# Driver_v0.net
KiCad netlist of a schematic drawn in Altium Designer
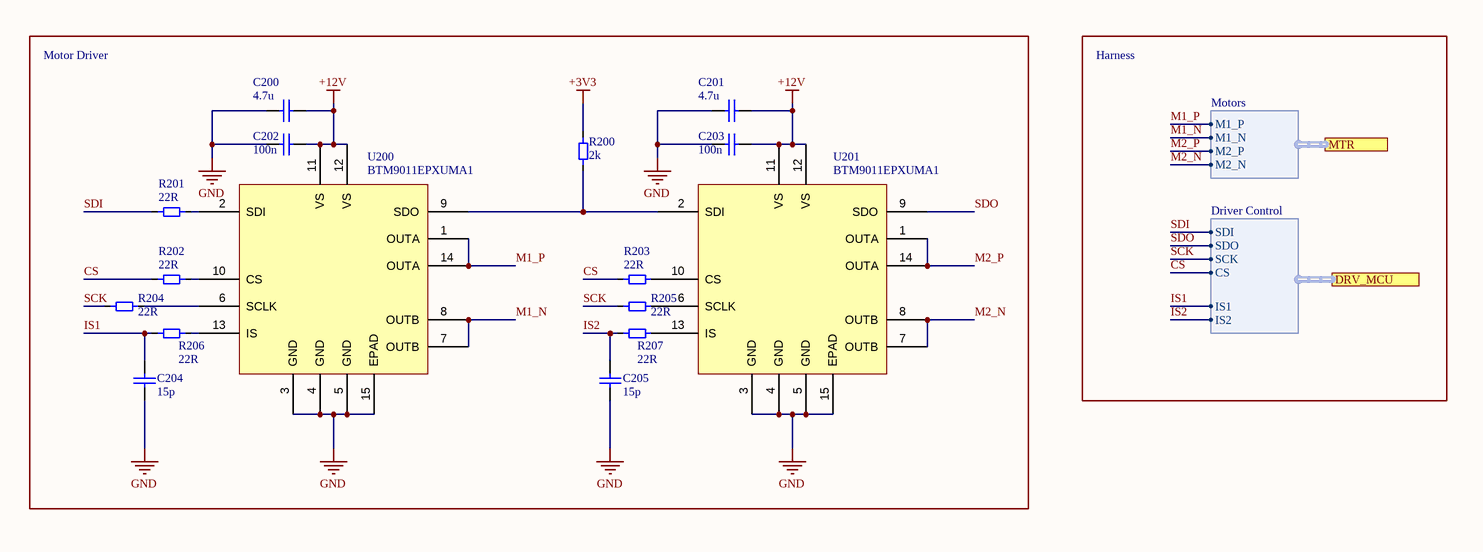
[diagram p0: Driver_v0.SchDoc, right]

(export (version "E")
  (design (tool "Eeschema 10.0.6"))
  (components
    (comp (ref "C200")
      (value "4.7u")
      (footprint "MLCC_0603_M")
      (description "MLCC, 0603, 4.7u, 10%, 35V, X5R")
      (fields (field (name "TOLERANCE") "10%") (field (name "VOLTAGE") "35V"))
      (libsource (lib "Krakul Vault") (part "CAPACITOR_NONPOL_IEC"))
    )
    (comp (ref "C201")
      (value "4.7u")
      (footprint "MLCC_0603_M")
      (description "MLCC, 0603, 4.7u, 10%, 35V, X5R")
      (fields (field (name "TOLERANCE") "10%") (field (name "VOLTAGE") "35V"))
      (libsource (lib "Krakul Vault") (part "CAPACITOR_NONPOL_IEC"))
    )
    (comp (ref "C202")
      (value "100n")
      (footprint "MLCC_0603_M")
      (description "MLCC, 0603, 100n, 10%, 35V, X7R")
      (fields (field (name "MANUFACTURER") "Any") (field (name "VOLTAGE") "35V"))
      (libsource (lib "Krakul Vault") (part "CAPACITOR_NONPOL_IEC"))
    )
    (comp (ref "C203")
      (value "100n")
      (footprint "MLCC_0603_M")
      (description "MLCC, 0603, 100n, 10%, 35V, X7R")
      (fields (field (name "MANUFACTURER") "Any") (field (name "VOLTAGE") "35V"))
      (libsource (lib "Krakul Vault") (part "CAPACITOR_NONPOL_IEC"))
    )
    (comp (ref "C204")
      (value "15p")
      (footprint "MLCC_0603_M")
      (description "MLCC, 0603, 15p, 5%, 50V, C0G/NP0")
      (fields (field (name "MANUFACTURER") "Any") (field (name "VOLTAGE") "50V"))
      (libsource (lib "Krakul Vault") (part "CAPACITOR_NONPOL_IEC"))
    )
    (comp (ref "C205")
      (value "15p")
      (footprint "MLCC_0603_M")
      (description "MLCC, 0603, 15p, 5%, 50V, C0G/NP0")
      (fields (field (name "MANUFACTURER") "Any") (field (name "VOLTAGE") "50V"))
      (libsource (lib "Krakul Vault") (part "CAPACITOR_NONPOL_IEC"))
    )
    (comp (ref "R200")
      (value "2k")
      (footprint "Resistor_0603_M")
      (description "Resistor, 0603, 2k, 1%, 1/10W")
      (fields (field (name "MANUFACTURER") "Any") (field (name "POWER") "100mW"))
      (libsource (lib "Krakul Vault") (part "RESISTOR_GENERIC_IEC"))
    )
    (comp (ref "R201")
      (value "22R")
      (footprint "Resistor_0603_M")
      (description "Resistor, 0603, 22R, 1%, 1/10W")
      (fields (field (name "TOLERANCE") "1%") (field (name "MANUFACTURER") "Any"))
      (libsource (lib "Krakul Vault") (part "RESISTOR_GENERIC_IEC"))
    )
    (comp (ref "R202")
      (value "22R")
      (footprint "Resistor_0603_M")
      (description "Resistor, 0603, 22R, 1%, 1/10W")
      (fields (field (name "TOLERANCE") "1%") (field (name "MANUFACTURER") "Any"))
      (libsource (lib "Krakul Vault") (part "RESISTOR_GENERIC_IEC"))
    )
    (comp (ref "R203")
      (value "22R")
      (footprint "Resistor_0603_M")
      (description "Resistor, 0603, 22R, 1%, 1/10W")
      (fields (field (name "TOLERANCE") "1%") (field (name "MANUFACTURER") "Any"))
      (libsource (lib "Krakul Vault") (part "RESISTOR_GENERIC_IEC"))
    )
    (comp (ref "R204")
      (value "22R")
      (footprint "Resistor_0603_M")
      (description "Resistor, 0603, 22R, 1%, 1/10W")
      (fields (field (name "TOLERANCE") "1%") (field (name "MANUFACTURER") "Any"))
      (libsource (lib "Krakul Vault") (part "RESISTOR_GENERIC_IEC"))
    )
    (comp (ref "R205")
      (value "22R")
      (footprint "Resistor_0603_M")
      (description "Resistor, 0603, 22R, 1%, 1/10W")
      (fields (field (name "TOLERANCE") "1%") (field (name "MANUFACTURER") "Any"))
      (libsource (lib "Krakul Vault") (part "RESISTOR_GENERIC_IEC"))
    )
    (comp (ref "R206")
      (value "22R")
      (footprint "Resistor_0603_M")
      (description "Resistor, 0603, 22R, 1%, 1/10W")
      (fields (field (name "TOLERANCE") "1%") (field (name "MANUFACTURER") "Any"))
      (libsource (lib "Krakul Vault") (part "RESISTOR_GENERIC_IEC"))
    )
    (comp (ref "R207")
      (value "22R")
      (footprint "Resistor_0603_M")
      (description "Resistor, 0603, 22R, 1%, 1/10W")
      (fields (field (name "TOLERANCE") "1%") (field (name "MANUFACTURER") "Any"))
      (libsource (lib "Krakul Vault") (part "RESISTOR_GENERIC_IEC"))
    )
    (comp (ref "U200")
      (value "BTM9011EPXUMA1")
      (footprint "BTM9011EPXUMA1")
      (description "DC Mtr Drive, Brush, 150DEGC, TSSOPEP-14 Rohs Compliant: Yes")
      (fields (field (name "MANUFACTURER") "Infineon Technologies"))
      (libsource (lib "Krakul Vault") (part "BTM9011EPXUMA1"))
    )
    (comp (ref "U201")
      (value "BTM9011EPXUMA1")
      (footprint "BTM9011EPXUMA1")
      (description "DC Mtr Drive, Brush, 150DEGC, TSSOPEP-14 Rohs Compliant: Yes")
      (fields (field (name "MANUFACTURER") "Infineon Technologies"))
      (libsource (lib "Krakul Vault") (part "BTM9011EPXUMA1"))
    )
  )
  (nets
    (net (code "4") (name "+3V3") (class "Default")
      (node (ref "R200") (pin "2") (pinfunction "2_2") (pintype "passive"))
    )
    (net (code "5") (name "+12V") (class "Default")
      (node (ref "C200") (pin "2") (pinfunction "2_2") (pintype "passive"))
      (node (ref "C201") (pin "2") (pinfunction "2_2") (pintype "passive"))
      (node (ref "C202") (pin "2") (pinfunction "2_2") (pintype "passive"))
      (node (ref "C203") (pin "2") (pinfunction "2_2") (pintype "passive"))
      (node (ref "U200") (pin "11") (pinfunction "VS_11") (pintype "passive"))
      (node (ref "U200") (pin "12") (pinfunction "VS_12") (pintype "passive"))
      (node (ref "U201") (pin "11") (pinfunction "VS_11") (pintype "passive"))
      (node (ref "U201") (pin "12") (pinfunction "VS_12") (pintype "passive"))
    )
    (net (code "6") (name "/CS") (class "Default")
      (node (ref "R202") (pin "1") (pinfunction "1_1") (pintype "passive"))
      (node (ref "R203") (pin "1") (pinfunction "1_1") (pintype "passive"))
    )
    (net (code "7") (name "/IS1") (class "Default")
      (node (ref "C204") (pin "1") (pinfunction "1_1") (pintype "passive"))
      (node (ref "R206") (pin "1") (pinfunction "1_1") (pintype "passive"))
    )
    (net (code "8") (name "/IS2") (class "Default")
      (node (ref "C205") (pin "1") (pinfunction "1_1") (pintype "passive"))
      (node (ref "R207") (pin "1") (pinfunction "1_1") (pintype "passive"))
    )
    (net (code "9") (name "/M1_N") (class "Default")
      (node (ref "U200") (pin "7") (pinfunction "OUTB_7") (pintype "passive"))
      (node (ref "U200") (pin "8") (pinfunction "OUTB_8") (pintype "passive"))
    )
    (net (code "10") (name "/M1_P") (class "Default")
      (node (ref "U200") (pin "1") (pinfunction "OUTA_1") (pintype "passive"))
      (node (ref "U200") (pin "14") (pinfunction "OUTA_14") (pintype "passive"))
    )
    (net (code "11") (name "/M2_N") (class "Default")
      (node (ref "U201") (pin "7") (pinfunction "OUTB_7") (pintype "passive"))
      (node (ref "U201") (pin "8") (pinfunction "OUTB_8") (pintype "passive"))
    )
    (net (code "12") (name "/M2_P") (class "Default")
      (node (ref "U201") (pin "1") (pinfunction "OUTA_1") (pintype "passive"))
      (node (ref "U201") (pin "14") (pinfunction "OUTA_14") (pintype "passive"))
    )
    (net (code "13") (name "/SCK") (class "Default")
      (node (ref "R204") (pin "1") (pinfunction "1_1") (pintype "passive"))
      (node (ref "R205") (pin "1") (pinfunction "1_1") (pintype "passive"))
    )
    (net (code "14") (name "/SDI") (class "Default")
      (node (ref "R201") (pin "1") (pinfunction "1_1") (pintype "passive"))
    )
    (net (code "15") (name "/SDO") (class "Default")
      (node (ref "U201") (pin "9") (pinfunction "SDO_9") (pintype "passive"))
    )
    (net (code "18") (name "GND") (class "Default")
      (node (ref "C200") (pin "1") (pinfunction "1_1") (pintype "passive"))
      (node (ref "C201") (pin "1") (pinfunction "1_1") (pintype "passive"))
      (node (ref "C202") (pin "1") (pinfunction "1_1") (pintype "passive"))
      (node (ref "C203") (pin "1") (pinfunction "1_1") (pintype "passive"))
      (node (ref "C204") (pin "2") (pinfunction "2_2") (pintype "passive"))
      (node (ref "C205") (pin "2") (pinfunction "2_2") (pintype "passive"))
      (node (ref "U200") (pin "15") (pinfunction "EPAD_15") (pintype "passive"))
      (node (ref "U200") (pin "3") (pinfunction "GND_3") (pintype "passive"))
      (node (ref "U200") (pin "4") (pinfunction "GND_4") (pintype "passive"))
      (node (ref "U200") (pin "5") (pinfunction "GND_5") (pintype "passive"))
      (node (ref "U201") (pin "15") (pinfunction "EPAD_15") (pintype "passive"))
      (node (ref "U201") (pin "3") (pinfunction "GND_3") (pintype "passive"))
      (node (ref "U201") (pin "4") (pinfunction "GND_4") (pintype "passive"))
      (node (ref "U201") (pin "5") (pinfunction "GND_5") (pintype "passive"))
    )
    (net (code "19") (name "Net-(U200-CS)") (class "Default")
      (node (ref "R202") (pin "2") (pinfunction "2_2") (pintype "passive"))
      (node (ref "U200") (pin "10") (pinfunction "CS_10") (pintype "passive"))
    )
    (net (code "20") (name "Net-(U200-IS)") (class "Default")
      (node (ref "R206") (pin "2") (pinfunction "2_2") (pintype "passive"))
      (node (ref "U200") (pin "13") (pinfunction "IS_13") (pintype "passive"))
    )
    (net (code "21") (name "Net-(U200-SCLK)") (class "Default")
      (node (ref "R204") (pin "2") (pinfunction "2_2") (pintype "passive"))
      (node (ref "U200") (pin "6") (pinfunction "SCLK_6") (pintype "passive"))
    )
    (net (code "22") (name "Net-(U200-SDI)") (class "Default")
      (node (ref "R201") (pin "2") (pinfunction "2_2") (pintype "passive"))
      (node (ref "U200") (pin "2") (pinfunction "SDI_2") (pintype "passive"))
    )
    (net (code "23") (name "Net-(U200-SDO)") (class "Default")
      (node (ref "R200") (pin "1") (pinfunction "1_1") (pintype "passive"))
      (node (ref "U200") (pin "9") (pinfunction "SDO_9") (pintype "passive"))
      (node (ref "U201") (pin "2") (pinfunction "SDI_2") (pintype "passive"))
    )
    (net (code "24") (name "Net-(U201-CS)") (class "Default")
      (node (ref "R203") (pin "2") (pinfunction "2_2") (pintype "passive"))
      (node (ref "U201") (pin "10") (pinfunction "CS_10") (pintype "passive"))
    )
    (net (code "25") (name "Net-(U201-IS)") (class "Default")
      (node (ref "R207") (pin "2") (pinfunction "2_2") (pintype "passive"))
      (node (ref "U201") (pin "13") (pinfunction "IS_13") (pintype "passive"))
    )
    (net (code "26") (name "Net-(U201-SCLK)") (class "Default")
      (node (ref "R205") (pin "2") (pinfunction "2_2") (pintype "passive"))
      (node (ref "U201") (pin "6") (pinfunction "SCLK_6") (pintype "passive"))
    )
  )
)
